# design.net
KiCad netlist of a schematic drawn in Altium Designer
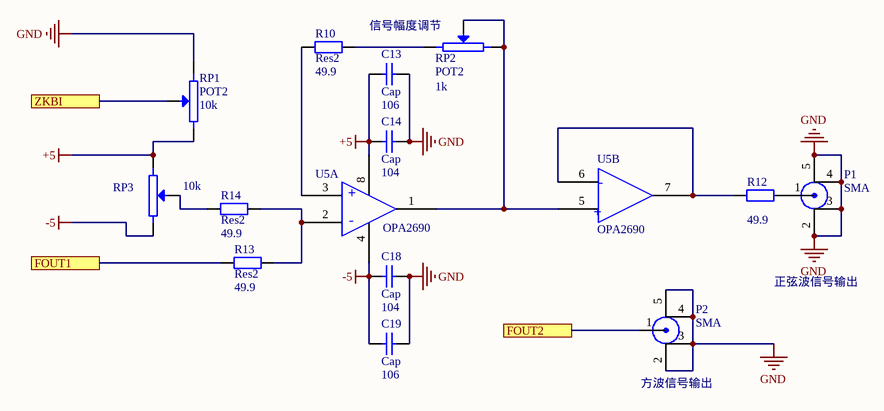
[diagram p0: 信号输出调理电路.SchDoc]

(export (version "E")
  (design (tool "Eeschema 10.0.6"))
  (components
    (comp (ref "C13")
      (value "Cap")
      (footprint "C0805")
      (description "Capacitor")
      (fields (field (name "ALTIUM_VALUE") "106") (field (name "PUBLISHER") "Altium Limited"))
      (libsource (lib "基于SMT32的DDS信号源原理图库") (part "Cap"))
    )
    (comp (ref "C14")
      (value "Cap")
      (footprint "C0805")
      (description "Capacitor")
      (fields (field (name "ALTIUM_VALUE") "104") (field (name "PUBLISHER") "Altium Limited"))
      (libsource (lib "基于SMT32的DDS信号源原理图库") (part "Cap"))
    )
    (comp (ref "C18")
      (value "Cap")
      (footprint "C0805")
      (description "Capacitor")
      (fields (field (name "ALTIUM_VALUE") "104") (field (name "PUBLISHER") "Altium Limited"))
      (libsource (lib "基于SMT32的DDS信号源原理图库") (part "Cap"))
    )
    (comp (ref "C19")
      (value "Cap")
      (footprint "C0805")
      (description "Capacitor")
      (fields (field (name "ALTIUM_VALUE") "106") (field (name "PUBLISHER") "Altium Limited"))
      (libsource (lib "基于SMT32的DDS信号源原理图库") (part "Cap"))
    )
    (comp (ref "P1") (value "SMA") (footprint "SMA-KE") (libsource (lib "基于SMT32的DDS信号源原理图库") (part "SMA")))
    (comp (ref "P2") (value "SMA") (footprint "SMA-KE") (libsource (lib "基于SMT32的DDS信号源原理图库") (part "SMA")))
    (comp (ref "R10")
      (value "Res2")
      (footprint "6-0805_N")
      (description "Resistor")
      (fields (field (name "ALTIUM_VALUE") "49.9") (field (name "PUBLISHER") "Altium Limited"))
      (libsource (lib "基于SMT32的DDS信号源原理图库") (part "Res2"))
    )
    (comp (ref "R12")
      (value "49.9")
      (footprint "6-0805_N")
      (description "Resistor")
      (fields (field (name "Comment") "Res2") (field (name "PUBLISHER") "Altium Limited"))
      (libsource (lib "Miscellaneous Devices") (part "Res2"))
    )
    (comp (ref "R13")
      (value "Res2")
      (footprint "6-0805_N")
      (description "Resistor")
      (fields (field (name "ALTIUM_VALUE") "49.9") (field (name "PUBLISHER") "Altium Limited"))
      (libsource (lib "基于SMT32的DDS信号源原理图库") (part "Res2"))
    )
    (comp (ref "R14")
      (value "Res2")
      (footprint "6-0805_N")
      (description "Resistor")
      (fields (field (name "ALTIUM_VALUE") "49.9") (field (name "PUBLISHER") "Altium Limited"))
      (libsource (lib "基于SMT32的DDS信号源原理图库") (part "Res2"))
    )
    (comp (ref "RP1")
      (value "POT2")
      (footprint "VR7")
      (description "Potentiometer")
      (fields (field (name "ALTIUM_VALUE") "10k"))
      (libsource (lib "基于SMT32的DDS信号源原理图库") (part "POT2"))
    )
    (comp (ref "RP2")
      (value "POT2")
      (footprint "VR7")
      (description "Potentiometer")
      (fields (field (name "ALTIUM_VALUE") "1k"))
      (libsource (lib "基于SMT32的DDS信号源原理图库") (part "POT2"))
    )
    (comp (ref "RP3")
      (value "10k")
      (footprint "VR7")
      (description "Potentiometer")
      (fields (field (name "Comment") "POT2"))
      (libsource (lib "刘涛20181107") (part "POT2"))
    )
    (comp (ref "U5")
      (value "OPA2690")
      (footprint "SO-8")
      (libsource (lib "基于SMT32的DDS信号源原理图库") (part "OPA2690"))
    )
  )
  (nets
    (net (code "1") (name "+5") (class "Default")
      (node (ref "C13") (pin "2") (pinfunction "2_2") (pintype "passive"))
      (node (ref "C14") (pin "2") (pinfunction "2_2") (pintype "passive"))
      (node (ref "RP1") (pin "1") (pinfunction "1_1") (pintype "passive"))
      (node (ref "RP3") (pin "1") (pinfunction "1_1") (pintype "passive"))
      (node (ref "U5") (pin "8") (pintype "passive"))
    )
    (net (code "2") (name "-5") (class "Default")
      (node (ref "C18") (pin "2") (pinfunction "2_2") (pintype "passive"))
      (node (ref "C19") (pin "2") (pinfunction "2_2") (pintype "passive"))
      (node (ref "RP3") (pin "2") (pinfunction "2_2") (pintype "passive"))
      (node (ref "U5") (pin "4") (pintype "passive"))
    )
    (net (code "3") (name "/FOUT1") (class "Default")
      (node (ref "R13") (pin "1") (pinfunction "1_1") (pintype "passive"))
    )
    (net (code "4") (name "/FOUT2") (class "Default") (node (ref "P2") (pin "1") (pintype "passive")))
    (net (code "5") (name "/ZKBI") (class "Default")
      (node (ref "RP1") (pin "3") (pinfunction "3_3") (pintype "passive"))
    )
    (net (code "6") (name "GND") (class "Default")
      (node (ref "C13") (pin "1") (pinfunction "1_1") (pintype "passive"))
      (node (ref "C14") (pin "1") (pinfunction "1_1") (pintype "passive"))
      (node (ref "C18") (pin "1") (pinfunction "1_1") (pintype "passive"))
      (node (ref "C19") (pin "1") (pinfunction "1_1") (pintype "passive"))
      (node (ref "P1") (pin "2") (pintype "passive"))
      (node (ref "P1") (pin "3") (pintype "passive"))
      (node (ref "P1") (pin "4") (pintype "passive"))
      (node (ref "P1") (pin "5") (pintype "passive"))
      (node (ref "P2") (pin "2") (pintype "passive"))
      (node (ref "P2") (pin "3") (pintype "passive"))
      (node (ref "P2") (pin "4") (pintype "passive"))
      (node (ref "P2") (pin "5") (pintype "passive"))
      (node (ref "RP1") (pin "2") (pinfunction "2_2") (pintype "passive"))
    )
    (net (code "7") (name "Net-(P1-Pad1)") (class "Default")
      (node (ref "P1") (pin "1") (pintype "passive"))
      (node (ref "R12") (pin "2") (pinfunction "2_2") (pintype "passive"))
    )
    (net (code "8") (name "Net-(R10-Pad1)") (class "Default")
      (node (ref "R10") (pin "1") (pinfunction "1_1") (pintype "passive"))
      (node (ref "U5") (pin "3") (pintype "passive"))
    )
    (net (code "9") (name "Net-(R10-Pad2)") (class "Default")
      (node (ref "R10") (pin "2") (pinfunction "2_2") (pintype "passive"))
      (node (ref "RP2") (pin "1") (pinfunction "1_1") (pintype "passive"))
    )
    (net (code "10") (name "Net-(R12-Pad1)") (class "Default")
      (node (ref "R12") (pin "1") (pinfunction "1_1") (pintype "passive"))
      (node (ref "U5") (pin "6") (pintype "passive"))
      (node (ref "U5") (pin "7") (pintype "passive"))
    )
    (net (code "11") (name "Net-(R13-Pad2)") (class "Default")
      (node (ref "R13") (pin "2") (pinfunction "2_2") (pintype "passive"))
      (node (ref "R14") (pin "2") (pinfunction "2_2") (pintype "passive"))
      (node (ref "U5") (pin "2") (pintype "passive"))
    )
    (net (code "12") (name "Net-(R14-Pad1)") (class "Default")
      (node (ref "R14") (pin "1") (pinfunction "1_1") (pintype "passive"))
      (node (ref "RP3") (pin "3") (pinfunction "3_3") (pintype "passive"))
    )
    (net (code "13") (name "Net-(RP2-Pad2)") (class "Default")
      (node (ref "RP2") (pin "2") (pinfunction "2_2") (pintype "passive"))
      (node (ref "RP2") (pin "3") (pinfunction "3_3") (pintype "passive"))
      (node (ref "U5") (pin "1") (pintype "passive"))
      (node (ref "U5") (pin "5") (pintype "passive"))
    )
  )
)
